# Motor_driver.net
KiCad netlist of a schematic drawn in EAGLE
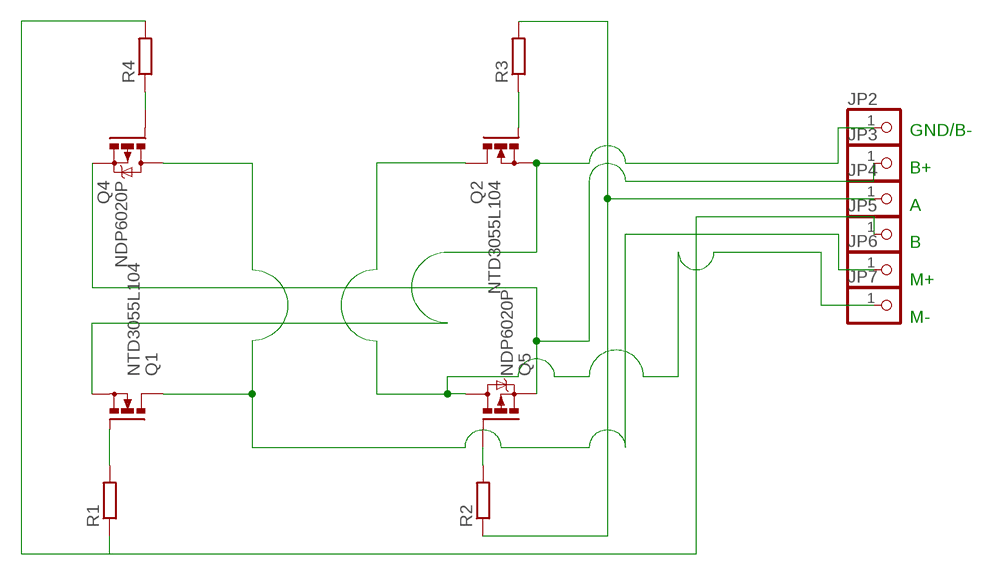
[diagram p0: schematic, sheet 1]

(export (version "E")
  (design (tool "Eeschema 10.0.6"))
  (components
    (comp (ref "JP2")
      (value "PINHD-1X1")
      (footprint "eagle-import:1X01")
      (libsource (lib "eagle-import") (part "PINHD-1X1"))
    )
    (comp (ref "JP3")
      (value "PINHD-1X1")
      (footprint "eagle-import:1X01")
      (libsource (lib "eagle-import") (part "PINHD-1X1"))
    )
    (comp (ref "JP4")
      (value "PINHD-1X1")
      (footprint "eagle-import:1X01")
      (libsource (lib "eagle-import") (part "PINHD-1X1"))
    )
    (comp (ref "JP5")
      (value "PINHD-1X1")
      (footprint "eagle-import:1X01")
      (libsource (lib "eagle-import") (part "PINHD-1X1"))
    )
    (comp (ref "JP6")
      (value "PINHD-1X1")
      (footprint "eagle-import:1X01")
      (libsource (lib "eagle-import") (part "PINHD-1X1"))
    )
    (comp (ref "JP7")
      (value "PINHD-1X1")
      (footprint "eagle-import:1X01")
      (libsource (lib "eagle-import") (part "PINHD-1X1"))
    )
    (comp (ref "Q1")
      (value "NTD3055L104")
      (footprint "eagle-import:TO220BV")
      (libsource (lib "eagle-import") (part "NTD3055L104"))
    )
    (comp (ref "Q2")
      (value "NTD3055L104")
      (footprint "eagle-import:TO220BV")
      (libsource (lib "eagle-import") (part "NTD3055L104"))
    )
    (comp (ref "Q4")
      (value "NDP6020P")
      (footprint "eagle-import:TO220BV")
      (libsource (lib "eagle-import") (part "IRF9530"))
    )
    (comp (ref "Q5")
      (value "NDP6020P")
      (footprint "eagle-import:TO220BV")
      (libsource (lib "eagle-import") (part "IRF9530"))
    )
    (comp (ref "R1")
      (value "R-EU_0204/2V")
      (footprint "eagle-import:0204V")
      (libsource (lib "eagle-import") (part "R-EU_0204/2V"))
    )
    (comp (ref "R2")
      (value "R-EU_0204/2V")
      (footprint "eagle-import:0204V")
      (libsource (lib "eagle-import") (part "R-EU_0204/2V"))
    )
    (comp (ref "R3")
      (value "R-EU_0204/2V")
      (footprint "eagle-import:0204V")
      (libsource (lib "eagle-import") (part "R-EU_0204/2V"))
    )
    (comp (ref "R4")
      (value "R-EU_0204/2V")
      (footprint "eagle-import:0204V")
      (libsource (lib "eagle-import") (part "R-EU_0204/2V"))
    )
  )
  (nets
    (net (code "1") (name "Net-(JP2-Pad1)") (class "Default")
      (node (ref "JP2") (pin "1") (pinfunction "1_1") (pintype "passive"))
      (node (ref "Q1") (pin "S") (pinfunction "S_S") (pintype "passive"))
      (node (ref "Q2") (pin "S") (pinfunction "S_S") (pintype "passive"))
    )
    (net (code "2") (name "Net-(JP3-Pad1)") (class "Default")
      (node (ref "JP3") (pin "1") (pinfunction "1_1") (pintype "passive"))
      (node (ref "Q4") (pin "S") (pinfunction "S_S") (pintype "passive"))
      (node (ref "Q5") (pin "S") (pinfunction "S_S") (pintype "passive"))
    )
    (net (code "3") (name "Net-(JP4-Pad1)") (class "Default")
      (node (ref "JP4") (pin "1") (pinfunction "1_1") (pintype "passive"))
      (node (ref "R2") (pin "1") (pinfunction "1_1") (pintype "passive"))
      (node (ref "R3") (pin "2") (pinfunction "2_2") (pintype "passive"))
    )
    (net (code "4") (name "Net-(JP5-Pad1)") (class "Default")
      (node (ref "JP5") (pin "1") (pinfunction "1_1") (pintype "passive"))
      (node (ref "R1") (pin "1") (pinfunction "1_1") (pintype "passive"))
      (node (ref "R4") (pin "2") (pinfunction "2_2") (pintype "passive"))
    )
    (net (code "5") (name "Net-(JP6-Pad1)") (class "Default")
      (node (ref "JP6") (pin "1") (pinfunction "1_1") (pintype "passive"))
      (node (ref "Q1") (pin "D") (pinfunction "D_D") (pintype "passive"))
      (node (ref "Q4") (pin "D") (pinfunction "D_D") (pintype "passive"))
    )
    (net (code "6") (name "Net-(JP7-Pad1)") (class "Default")
      (node (ref "JP7") (pin "1") (pinfunction "1_1") (pintype "passive"))
      (node (ref "Q2") (pin "D") (pinfunction "D_D") (pintype "passive"))
      (node (ref "Q5") (pin "D") (pinfunction "D_D") (pintype "passive"))
    )
    (net (code "7") (name "Net-(Q1-PadG)") (class "Default")
      (node (ref "Q1") (pin "G") (pinfunction "G_G") (pintype "passive"))
      (node (ref "R1") (pin "2") (pinfunction "2_2") (pintype "passive"))
    )
    (net (code "8") (name "Net-(Q2-PadG)") (class "Default")
      (node (ref "Q2") (pin "G") (pinfunction "G_G") (pintype "passive"))
      (node (ref "R3") (pin "1") (pinfunction "1_1") (pintype "passive"))
    )
    (net (code "9") (name "Net-(Q4-PadG)") (class "Default")
      (node (ref "Q4") (pin "G") (pinfunction "G_G") (pintype "passive"))
      (node (ref "R4") (pin "1") (pinfunction "1_1") (pintype "passive"))
    )
    (net (code "10") (name "Net-(Q5-PadG)") (class "Default")
      (node (ref "Q5") (pin "G") (pinfunction "G_G") (pintype "passive"))
      (node (ref "R2") (pin "2") (pinfunction "2_2") (pintype "passive"))
    )
  )
)
